# 5v_dc.net
KiCad netlist of a schematic drawn in EAGLE
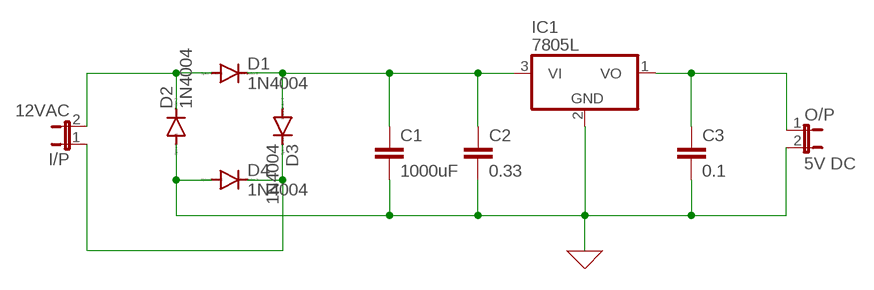
[diagram p0: schematic, sheet 1]

(export (version "E")
  (design (tool "Eeschema 10.0.6"))
  (components
    (comp (ref "C1")
      (value "1000uF")
      (footprint "eagle-import:C2.5-3")
      (libsource (lib "eagle-import") (part "C2,5-3"))
    )
    (comp (ref "C2")
      (value "0.33")
      (footprint "eagle-import:C2.5-3")
      (libsource (lib "eagle-import") (part "C2,5-3"))
    )
    (comp (ref "C3")
      (value "0.1")
      (footprint "eagle-import:C2.5-3")
      (libsource (lib "eagle-import") (part "C2,5-3"))
    )
    (comp (ref "D1")
      (value "1N4004")
      (footprint "eagle-import:DO41-10")
      (libsource (lib "eagle-import") (part "1N4004"))
    )
    (comp (ref "D2")
      (value "1N4004")
      (footprint "eagle-import:DO41-10")
      (libsource (lib "eagle-import") (part "1N4004"))
    )
    (comp (ref "D3")
      (value "1N4004")
      (footprint "eagle-import:DO41-10")
      (libsource (lib "eagle-import") (part "1N4004"))
    )
    (comp (ref "D4")
      (value "1N4004")
      (footprint "eagle-import:DO41-10")
      (libsource (lib "eagle-import") (part "1N4004"))
    )
    (comp (ref "I/P")
      (value "12VAC")
      (footprint "eagle-import:JP1")
      (libsource (lib "eagle-import") (part "JP1E"))
    )
    (comp (ref "IC1")
      (value "7805L")
      (footprint "eagle-import:TO92")
      (libsource (lib "eagle-import") (part "78L05"))
    )
    (comp (ref "O/P")
      (value "5V DC")
      (footprint "eagle-import:JP1")
      (libsource (lib "eagle-import") (part "JP1E"))
    )
  )
  (nets
    (net (code "1") (name "GND") (class "Default")
      (node (ref "C1") (pin "2") (pinfunction "2_2") (pintype "passive"))
      (node (ref "C2") (pin "2") (pinfunction "2_2") (pintype "passive"))
      (node (ref "C3") (pin "2") (pinfunction "2_2") (pintype "passive"))
      (node (ref "D2") (pin "A") (pinfunction "A_A") (pintype "passive"))
      (node (ref "D4") (pin "A") (pinfunction "A_A") (pintype "passive"))
      (node (ref "IC1") (pin "2") (pinfunction "GND_2") (pintype "passive"))
      (node (ref "O/P") (pin "2") (pinfunction "2_2") (pintype "passive"))
    )
    (net (code "2") (name "Net-(D1-PadA)") (class "Default")
      (node (ref "D1") (pin "A") (pinfunction "A_A") (pintype "passive"))
      (node (ref "D2") (pin "C") (pinfunction "C_C") (pintype "passive"))
      (node (ref "I/P") (pin "2") (pinfunction "2_2") (pintype "passive"))
    )
    (net (code "3") (name "Net-(D3-PadC)") (class "Default")
      (node (ref "D3") (pin "C") (pinfunction "C_C") (pintype "passive"))
      (node (ref "D4") (pin "C") (pinfunction "C_C") (pintype "passive"))
      (node (ref "I/P") (pin "1") (pinfunction "1_1") (pintype "passive"))
    )
    (net (code "4") (name "Net-(IC1-VI)") (class "Default")
      (node (ref "C1") (pin "1") (pinfunction "1_1") (pintype "passive"))
      (node (ref "C2") (pin "1") (pinfunction "1_1") (pintype "passive"))
      (node (ref "D1") (pin "C") (pinfunction "C_C") (pintype "passive"))
      (node (ref "D3") (pin "A") (pinfunction "A_A") (pintype "passive"))
      (node (ref "IC1") (pin "3") (pinfunction "VI_3") (pintype "input"))
    )
    (net (code "5") (name "Net-(IC1-VO)") (class "Default")
      (node (ref "C3") (pin "1") (pinfunction "1_1") (pintype "passive"))
      (node (ref "IC1") (pin "1") (pinfunction "VO_1") (pintype "passive"))
      (node (ref "O/P") (pin "1") (pinfunction "1_1") (pintype "passive"))
    )
  )
)
